# Sensor_LED_PCB.net
KiCad netlist of a schematic drawn in EAGLE
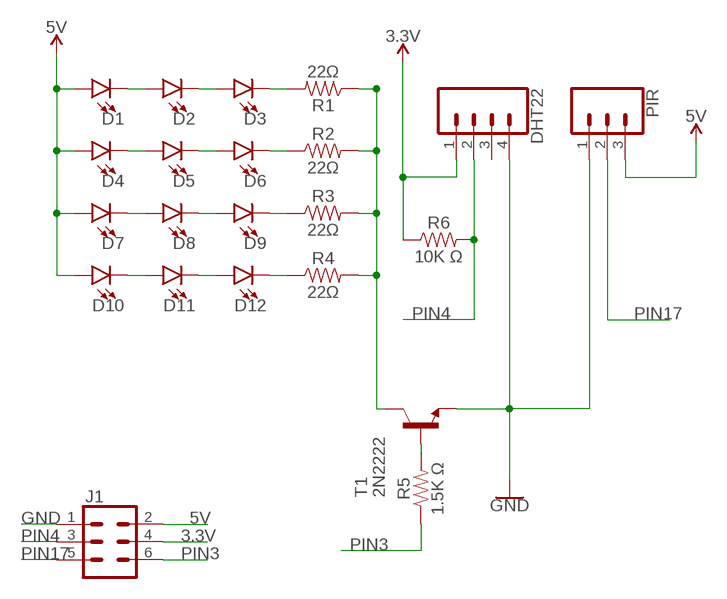
[diagram p0: schematic, sheet 1]

(export (version "E")
  (design (tool "Eeschema 10.0.6"))
  (components
    (comp (ref "D1")
      (value "LED5MM")
      (footprint "eagle-import:LED_5MM")
      (libsource (lib "eagle-import") (part "LED5MM"))
    )
    (comp (ref "D2")
      (value "LED5MM")
      (footprint "eagle-import:LED_5MM")
      (libsource (lib "eagle-import") (part "LED5MM"))
    )
    (comp (ref "D3")
      (value "LED5MM")
      (footprint "eagle-import:LED_5MM")
      (libsource (lib "eagle-import") (part "LED5MM"))
    )
    (comp (ref "D4")
      (value "LED5MM")
      (footprint "eagle-import:LED_5MM")
      (libsource (lib "eagle-import") (part "LED5MM"))
    )
    (comp (ref "D5")
      (value "LED5MM")
      (footprint "eagle-import:LED_5MM")
      (libsource (lib "eagle-import") (part "LED5MM"))
    )
    (comp (ref "D6")
      (value "LED5MM")
      (footprint "eagle-import:LED_5MM")
      (libsource (lib "eagle-import") (part "LED5MM"))
    )
    (comp (ref "D7")
      (value "LED5MM")
      (footprint "eagle-import:LED_5MM")
      (libsource (lib "eagle-import") (part "LED5MM"))
    )
    (comp (ref "D8")
      (value "LED5MM")
      (footprint "eagle-import:LED_5MM")
      (libsource (lib "eagle-import") (part "LED5MM"))
    )
    (comp (ref "D9")
      (value "LED5MM")
      (footprint "eagle-import:LED_5MM")
      (libsource (lib "eagle-import") (part "LED5MM"))
    )
    (comp (ref "D10")
      (value "LED5MM")
      (footprint "eagle-import:LED_5MM")
      (libsource (lib "eagle-import") (part "LED5MM"))
    )
    (comp (ref "D11")
      (value "LED5MM")
      (footprint "eagle-import:LED_5MM")
      (libsource (lib "eagle-import") (part "LED5MM"))
    )
    (comp (ref "D12")
      (value "LED5MM")
      (footprint "eagle-import:LED_5MM")
      (libsource (lib "eagle-import") (part "LED5MM"))
    )
    (comp (ref "DHT22")
      (value "CONN_04LONGPADS")
      (footprint "eagle-import:1X04_LONGPADS")
      (libsource (lib "eagle-import") (part "CONN_04LONGPADS"))
    )
    (comp (ref "J1")
      (value "CONN_03X2SHROUD")
      (footprint "eagle-import:2X3-SHROUDED")
      (libsource (lib "eagle-import") (part "CONN_03X2SHROUD"))
    )
    (comp (ref "PIR")
      (value "CONN_03LONGPADS")
      (footprint "eagle-import:1X03_LONGPADS")
      (libsource (lib "eagle-import") (part "CONN_03LONGPADS"))
    )
    (comp (ref "R1")
      (value "22Ω")
      (footprint "eagle-import:AXIAL-0.3-KIT")
      (libsource (lib "eagle-import") (part "10OHM-HORIZ_KIT-1/4W-1%"))
    )
    (comp (ref "R2")
      (value "22Ω")
      (footprint "eagle-import:AXIAL-0.3-KIT")
      (libsource (lib "eagle-import") (part "10OHM-HORIZ_KIT-1/4W-1%"))
    )
    (comp (ref "R3")
      (value "22Ω")
      (footprint "eagle-import:AXIAL-0.3-KIT")
      (libsource (lib "eagle-import") (part "10OHM-HORIZ_KIT-1/4W-1%"))
    )
    (comp (ref "R4")
      (value "22Ω")
      (footprint "eagle-import:AXIAL-0.3-KIT")
      (libsource (lib "eagle-import") (part "10OHM-HORIZ_KIT-1/4W-1%"))
    )
    (comp (ref "R5")
      (value "1.5K Ω")
      (footprint "eagle-import:AXIAL-0.3-KIT")
      (libsource (lib "eagle-import") (part "10OHM-HORIZ_KIT-1/4W-1%"))
    )
    (comp (ref "R6")
      (value "10K Ω")
      (footprint "eagle-import:AXIAL-0.3-KIT")
      (libsource (lib "eagle-import") (part "10OHM-HORIZ_KIT-1/4W-1%"))
    )
    (comp (ref "T1")
      (value "2N2222")
      (footprint "eagle-import:TO92-EBC-OVAL")
      (libsource (lib "eagle-import") (part "2N2222"))
    )
  )
  (nets
    (net (code "1") (name "/PIN3") (class "Default")
      (node (ref "J1") (pin "6") (pinfunction "6_6") (pintype "bidirectional"))
      (node (ref "R5") (pin "P$1") (pinfunction "1_P$1") (pintype "passive"))
    )
    (net (code "2") (name "/PIN4") (class "Default")
      (node (ref "DHT22") (pin "2") (pinfunction "2_2") (pintype "passive"))
      (node (ref "J1") (pin "3") (pinfunction "3_3") (pintype "bidirectional"))
      (node (ref "R6") (pin "P$2") (pinfunction "2_P$2") (pintype "passive"))
    )
    (net (code "3") (name "/PIN17") (class "Default")
      (node (ref "J1") (pin "5") (pinfunction "5_5") (pintype "bidirectional"))
      (node (ref "PIR") (pin "2") (pinfunction "2_2") (pintype "passive"))
    )
    (net (code "4") (name "3.3V") (class "Default")
      (node (ref "DHT22") (pin "1") (pinfunction "1_1") (pintype "passive"))
      (node (ref "J1") (pin "4") (pinfunction "4_4") (pintype "bidirectional"))
      (node (ref "R6") (pin "P$1") (pinfunction "1_P$1") (pintype "passive"))
    )
    (net (code "5") (name "5V") (class "Default")
      (node (ref "D1") (pin "A") (pinfunction "A_A") (pintype "passive"))
      (node (ref "D10") (pin "A") (pinfunction "A_A") (pintype "passive"))
      (node (ref "D4") (pin "A") (pinfunction "A_A") (pintype "passive"))
      (node (ref "D7") (pin "A") (pinfunction "A_A") (pintype "passive"))
      (node (ref "J1") (pin "2") (pinfunction "2_2") (pintype "bidirectional"))
      (node (ref "PIR") (pin "3") (pinfunction "3_3") (pintype "passive"))
    )
    (net (code "6") (name "GND") (class "Default")
      (node (ref "DHT22") (pin "4") (pinfunction "4_4") (pintype "passive"))
      (node (ref "J1") (pin "1") (pinfunction "1_1") (pintype "bidirectional"))
      (node (ref "PIR") (pin "1") (pinfunction "1_1") (pintype "passive"))
      (node (ref "T1") (pin "E") (pinfunction "E_E") (pintype "passive"))
    )
    (net (code "7") (name "Net-(D1-C)") (class "Default")
      (node (ref "D1") (pin "K") (pinfunction "C_K") (pintype "passive"))
      (node (ref "D2") (pin "A") (pinfunction "A_A") (pintype "passive"))
    )
    (net (code "8") (name "Net-(D2-C)") (class "Default")
      (node (ref "D2") (pin "K") (pinfunction "C_K") (pintype "passive"))
      (node (ref "D3") (pin "A") (pinfunction "A_A") (pintype "passive"))
    )
    (net (code "9") (name "Net-(D3-C)") (class "Default")
      (node (ref "D3") (pin "K") (pinfunction "C_K") (pintype "passive"))
      (node (ref "R1") (pin "P$2") (pinfunction "2_P$2") (pintype "passive"))
    )
    (net (code "10") (name "Net-(D4-C)") (class "Default")
      (node (ref "D4") (pin "K") (pinfunction "C_K") (pintype "passive"))
      (node (ref "D5") (pin "A") (pinfunction "A_A") (pintype "passive"))
    )
    (net (code "11") (name "Net-(D5-C)") (class "Default")
      (node (ref "D5") (pin "K") (pinfunction "C_K") (pintype "passive"))
      (node (ref "D6") (pin "A") (pinfunction "A_A") (pintype "passive"))
    )
    (net (code "12") (name "Net-(D6-C)") (class "Default")
      (node (ref "D6") (pin "K") (pinfunction "C_K") (pintype "passive"))
      (node (ref "R2") (pin "P$1") (pinfunction "1_P$1") (pintype "passive"))
    )
    (net (code "13") (name "Net-(D7-C)") (class "Default")
      (node (ref "D7") (pin "K") (pinfunction "C_K") (pintype "passive"))
      (node (ref "D8") (pin "A") (pinfunction "A_A") (pintype "passive"))
    )
    (net (code "14") (name "Net-(D8-C)") (class "Default")
      (node (ref "D8") (pin "K") (pinfunction "C_K") (pintype "passive"))
      (node (ref "D9") (pin "A") (pinfunction "A_A") (pintype "passive"))
    )
    (net (code "15") (name "Net-(D9-C)") (class "Default")
      (node (ref "D9") (pin "K") (pinfunction "C_K") (pintype "passive"))
      (node (ref "R3") (pin "P$1") (pinfunction "1_P$1") (pintype "passive"))
    )
    (net (code "16") (name "Net-(D10-C)") (class "Default")
      (node (ref "D10") (pin "K") (pinfunction "C_K") (pintype "passive"))
      (node (ref "D11") (pin "A") (pinfunction "A_A") (pintype "passive"))
    )
    (net (code "17") (name "Net-(D11-C)") (class "Default")
      (node (ref "D11") (pin "K") (pinfunction "C_K") (pintype "passive"))
      (node (ref "D12") (pin "A") (pinfunction "A_A") (pintype "passive"))
    )
    (net (code "18") (name "Net-(D12-C)") (class "Default")
      (node (ref "D12") (pin "K") (pinfunction "C_K") (pintype "passive"))
      (node (ref "R4") (pin "P$1") (pinfunction "1_P$1") (pintype "passive"))
    )
    (net (code "19") (name "Net-(R1-1)") (class "Default")
      (node (ref "R1") (pin "P$1") (pinfunction "1_P$1") (pintype "passive"))
      (node (ref "R2") (pin "P$2") (pinfunction "2_P$2") (pintype "passive"))
      (node (ref "R3") (pin "P$2") (pinfunction "2_P$2") (pintype "passive"))
      (node (ref "R4") (pin "P$2") (pinfunction "2_P$2") (pintype "passive"))
      (node (ref "T1") (pin "C") (pinfunction "C_C") (pintype "passive"))
    )
    (net (code "20") (name "Net-(R5-2)") (class "Default")
      (node (ref "R5") (pin "P$2") (pinfunction "2_P$2") (pintype "passive"))
      (node (ref "T1") (pin "B") (pinfunction "B_B") (pintype "passive"))
    )
    (net (code "21") (name "unconnected-(DHT22-Pad3)") (class "Default")
      (node (ref "DHT22") (pin "3") (pinfunction "3_3") (pintype "passive"))
    )
  )
)
